# alimentation.net
KiCad netlist of a schematic drawn in Altium Designer
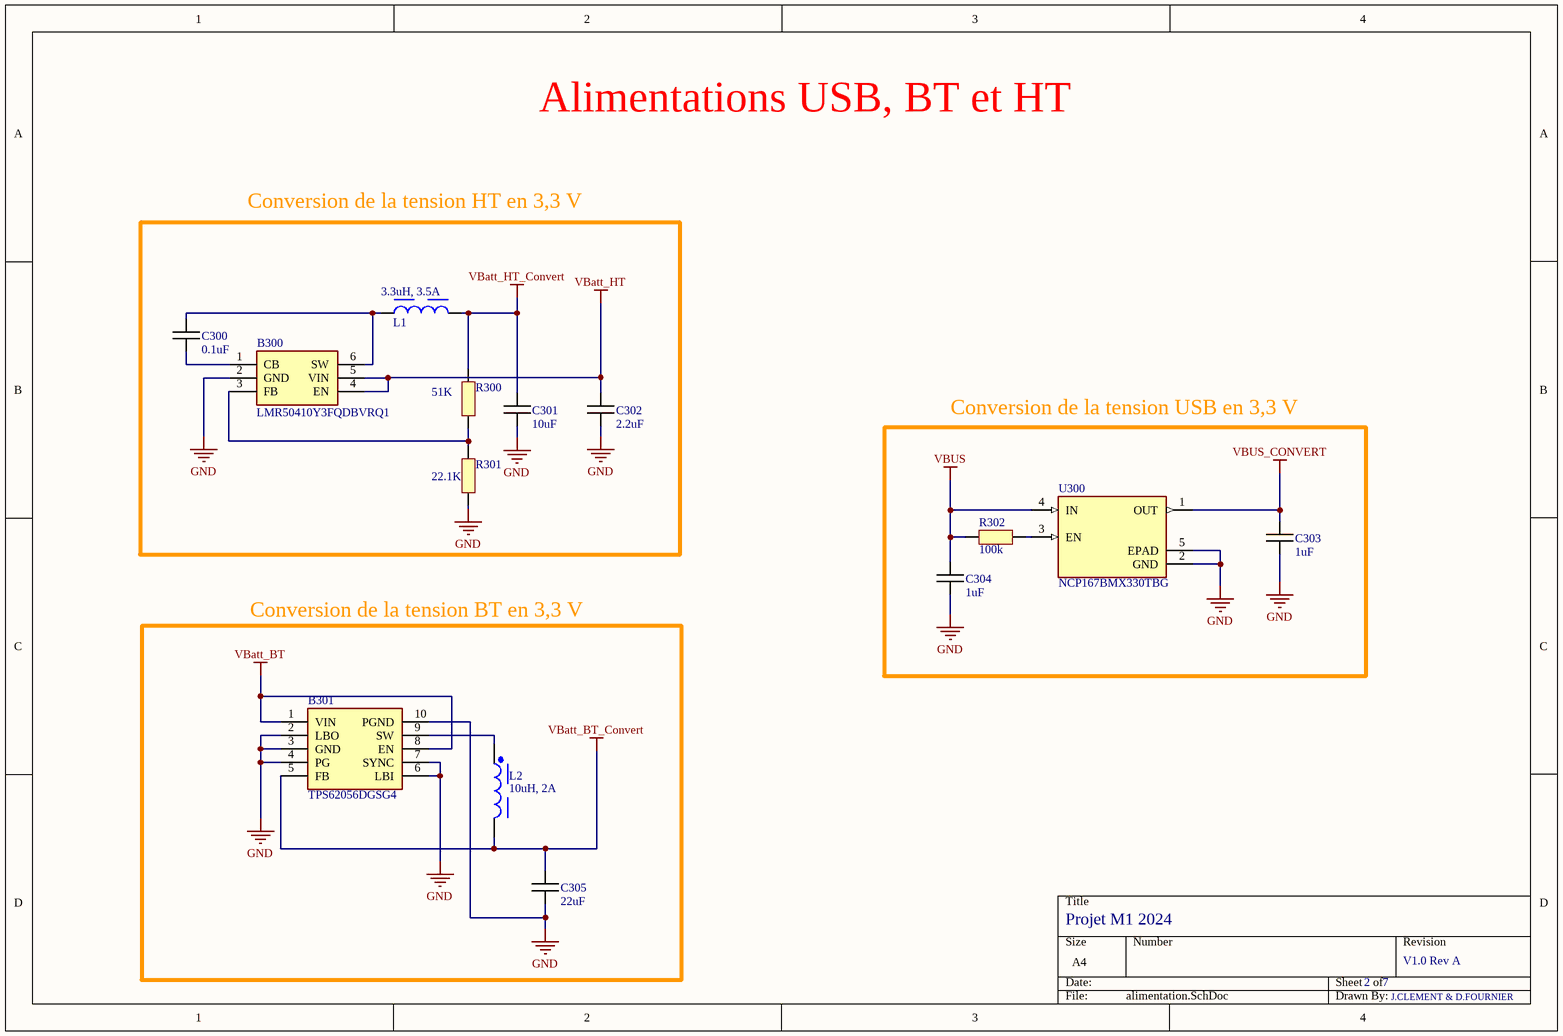
[diagram p0: alimentation.SchDoc]

(export (version "E")
  (design (tool "Eeschema 10.0.6"))
  (components
    (comp (ref "B300")
      (value "LMR50410Y3FQDBVRQ1")
      (footprint "SOT95P280X145-6N")
      (fields (field (name "MOUSER PART NUMBER") "595-R50410Y3FQDBVRQ1"))
      (libsource (lib "SCHLibrary") (part "LMR50410Y3FQDBVRQ1"))
    )
    (comp (ref "B301")
      (value "TPS62056DGSG4")
      (footprint "SOP50P490X110-10N")
      (fields (field (name "MOUSER PART NUMBER") "595-TPS62056DGSG4"))
      (libsource (lib "SCHLibrary") (part "TPS62056DGSG4"))
    )
    (comp (ref "C300")
      (value "0.1uF")
      (footprint "CAPA_0603")
      (libsource (lib "SCHLibrary") (part "Capacitor"))
    )
    (comp (ref "C301")
      (value "10uF")
      (footprint "CAPA_0603")
      (libsource (lib "SCHLibrary") (part "Capacitor"))
    )
    (comp (ref "C302")
      (value "2.2uF")
      (footprint "CAPA_0603")
      (libsource (lib "SCHLibrary") (part "Capacitor"))
    )
    (comp (ref "C303")
      (value "1uF")
      (footprint "CAPA_0603")
      (libsource (lib "SCHLibrary") (part "Capacitor"))
    )
    (comp (ref "C304")
      (value "1uF")
      (footprint "CAPA_0603")
      (libsource (lib "SCHLibrary") (part "Capacitor"))
    )
    (comp (ref "C305")
      (value "22uF")
      (footprint "CAPA_0603")
      (libsource (lib "SCHLibrary") (part "Capacitor"))
    )
    (comp (ref "L1")
      (value "3.3uH, 3.5A")
      (footprint "WE-LHMI_4020")
      (description "WE-LHMI SMT Power Inductor, size 4020, 3.3uH, 3.5A, 76mOhm")
      (fields
        (field (name "MANUFACTURER PART NUMBER") "74437324033")
        (field (name "MANUFACTURER") "Wurth Elektronik")
      )
      (libsource (lib "SCHLibrary") (part "74437324033"))
    )
    (comp (ref "L2")
      (value "10uH, 2A")
      (footprint "WE-PD_7345")
      (description "WE-PD SMT Power Inductor, size 7345, 10uH, 2A, 49mOhm")
      (fields
        (field (name "MANUFACTURER PART NUMBER") "74477710")
        (field (name "MANUFACTURER") "Wurth Elektronik")
      )
      (libsource (lib "SCHLibrary") (part "74477710"))
    )
    (comp (ref "R300") (value "51K") (footprint "RES_0603") (libsource (lib "SCHLibrary") (part "Resistor")))
    (comp (ref "R301")
      (value "22.1K")
      (footprint "RES_0603")
      (libsource (lib "SCHLibrary") (part "Resistor"))
    )
    (comp (ref "R302") (value "100k") (footprint "RES_0603") (libsource (lib "") (part "Resistor_1")))
    (comp (ref "U300")
      (value "NCP167BMX330TBG")
      (footprint "NCP167BMX330TBG")
      (description "Régulateurs de tension LDO LDO 700 MA ULTRA-LOW NOISE 3.3V")
      (libsource (lib "SCHLibrary") (part "NCP167BMX330TBG"))
    )
  )
  (nets
    (net (code "1") (name "GND") (class "Default")
      (node (ref "B300") (pin "2") (pinfunction "GND_2") (pintype "passive"))
      (node (ref "B301") (pin "10") (pinfunction "PGND_10") (pintype "passive"))
      (node (ref "B301") (pin "2") (pinfunction "LBO_2") (pintype "passive"))
      (node (ref "B301") (pin "3") (pinfunction "GND_3") (pintype "passive"))
      (node (ref "B301") (pin "4") (pinfunction "PG_4") (pintype "passive"))
      (node (ref "B301") (pin "6") (pinfunction "LBI_6") (pintype "passive"))
      (node (ref "B301") (pin "7") (pinfunction "SYNC_7") (pintype "passive"))
      (node (ref "C301") (pin "2") (pinfunction "2_2") (pintype "passive"))
      (node (ref "C302") (pin "2") (pinfunction "2_2") (pintype "passive"))
      (node (ref "C303") (pin "2") (pinfunction "2_2") (pintype "passive"))
      (node (ref "C304") (pin "2") (pinfunction "2_2") (pintype "passive"))
      (node (ref "C305") (pin "2") (pinfunction "2_2") (pintype "passive"))
      (node (ref "R301") (pin "1") (pinfunction "1_1") (pintype "passive"))
      (node (ref "U300") (pin "2") (pinfunction "GND_2") (pintype "power_in"))
      (node (ref "U300") (pin "5") (pinfunction "EPAD_5") (pintype "power_in"))
    )
    (net (code "2") (name "Net-(B300-CB)") (class "Default")
      (node (ref "B300") (pin "1") (pinfunction "CB_1") (pintype "passive"))
      (node (ref "C300") (pin "2") (pinfunction "2_2") (pintype "passive"))
    )
    (net (code "3") (name "Net-(B300-FB)") (class "Default")
      (node (ref "B300") (pin "3") (pinfunction "FB_3") (pintype "passive"))
      (node (ref "R300") (pin "1") (pinfunction "1_1") (pintype "passive"))
      (node (ref "R301") (pin "2") (pinfunction "2_2") (pintype "passive"))
    )
    (net (code "4") (name "Net-(B300-SW)") (class "Default")
      (node (ref "B300") (pin "6") (pinfunction "SW_6") (pintype "passive"))
      (node (ref "C300") (pin "1") (pinfunction "1_1") (pintype "passive"))
      (node (ref "L1") (pin "1") (pinfunction "1_1") (pintype "passive"))
    )
    (net (code "5") (name "Net-(B301-SW)") (class "Default")
      (node (ref "B301") (pin "9") (pinfunction "SW_9") (pintype "passive"))
      (node (ref "L2") (pin "1") (pinfunction "1_1") (pintype "passive"))
    )
    (net (code "6") (name "Net-(U300-EN)") (class "Default")
      (node (ref "R302") (pin "1") (pinfunction "1_1") (pintype "passive"))
      (node (ref "U300") (pin "3") (pinfunction "EN_3") (pintype "input"))
    )
    (net (code "7") (name "VBUS") (class "Default")
      (node (ref "C304") (pin "1") (pinfunction "1_1") (pintype "passive"))
      (node (ref "R302") (pin "2") (pinfunction "2_2") (pintype "passive"))
      (node (ref "U300") (pin "4") (pinfunction "IN_4") (pintype "input"))
    )
    (net (code "8") (name "VBUS_CONVERT") (class "Default")
      (node (ref "C303") (pin "1") (pinfunction "1_1") (pintype "passive"))
      (node (ref "U300") (pin "1") (pinfunction "OUT_1") (pintype "output"))
    )
    (net (code "9") (name "VBatt_BT") (class "Default")
      (node (ref "B301") (pin "1") (pinfunction "VIN_1") (pintype "passive"))
      (node (ref "B301") (pin "8") (pinfunction "EN_8") (pintype "passive"))
    )
    (net (code "10") (name "VBatt_BT_Convert") (class "Default")
      (node (ref "B301") (pin "5") (pinfunction "FB_5") (pintype "passive"))
      (node (ref "C305") (pin "1") (pinfunction "1_1") (pintype "passive"))
      (node (ref "L2") (pin "2") (pinfunction "2_2") (pintype "passive"))
    )
    (net (code "11") (name "VBatt_HT") (class "Default")
      (node (ref "B300") (pin "4") (pinfunction "EN_4") (pintype "passive"))
      (node (ref "B300") (pin "5") (pinfunction "VIN_5") (pintype "passive"))
      (node (ref "C302") (pin "1") (pinfunction "1_1") (pintype "passive"))
    )
    (net (code "12") (name "VBatt_HT_Convert") (class "Default")
      (node (ref "C301") (pin "1") (pinfunction "1_1") (pintype "passive"))
      (node (ref "L1") (pin "2") (pinfunction "2_2") (pintype "passive"))
      (node (ref "R300") (pin "2") (pinfunction "2_2") (pintype "passive"))
    )
  )
)
